# SMC1940-A.net
KiCad netlist of a schematic drawn in Altium Designer
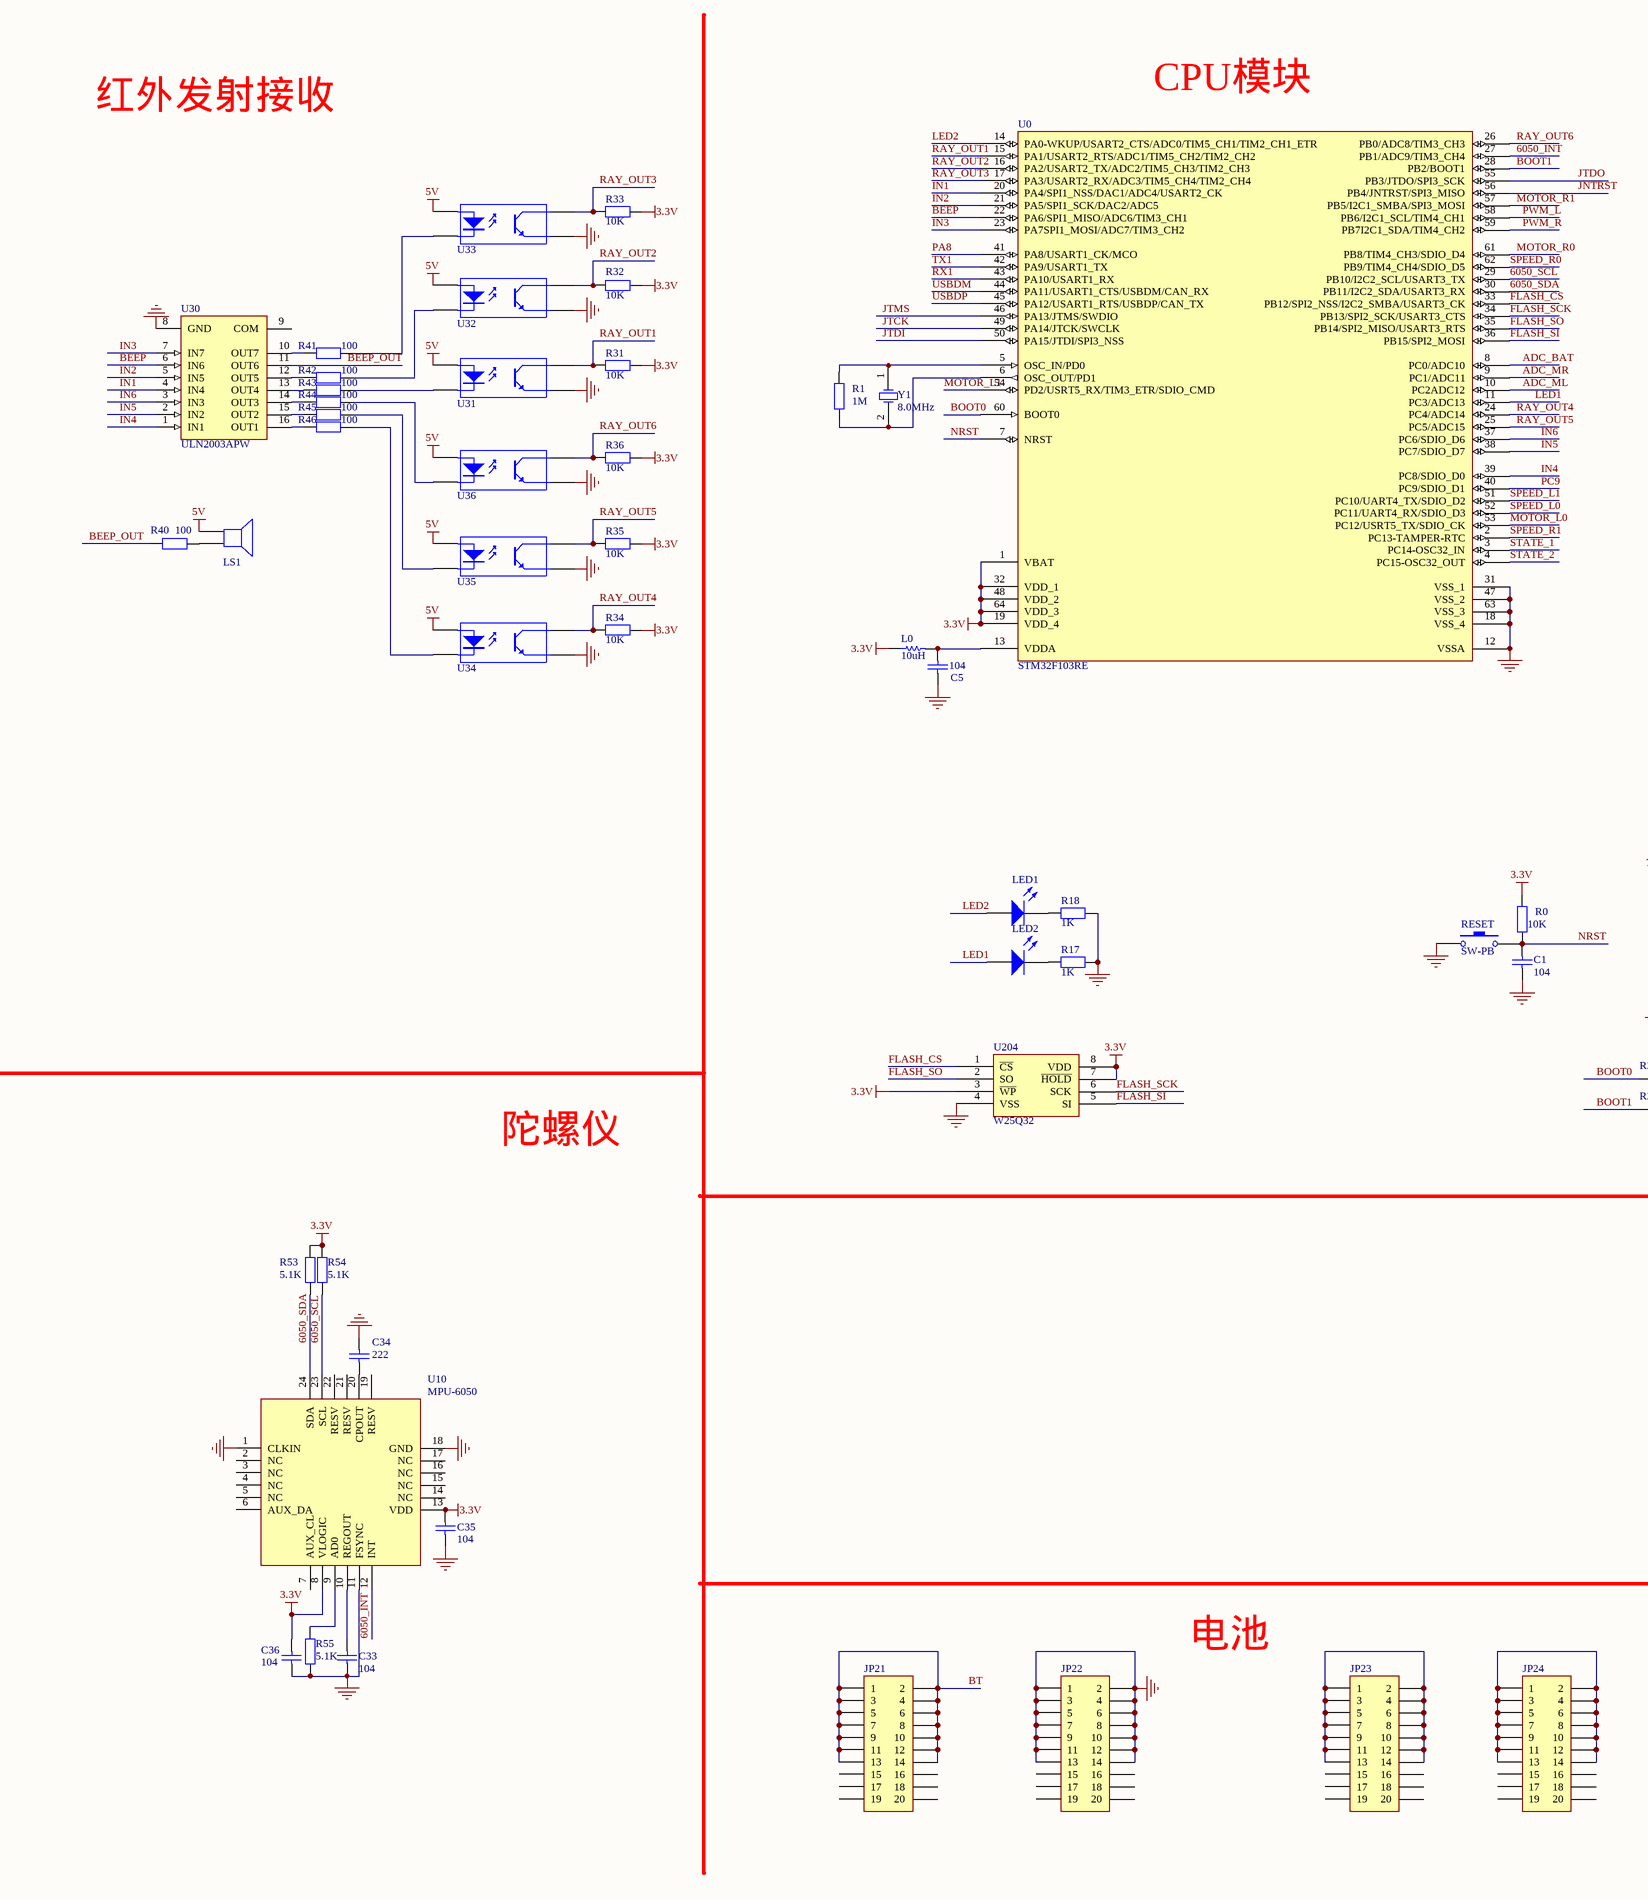
[diagram p0: SMC1940-A.SCHDOC, left]
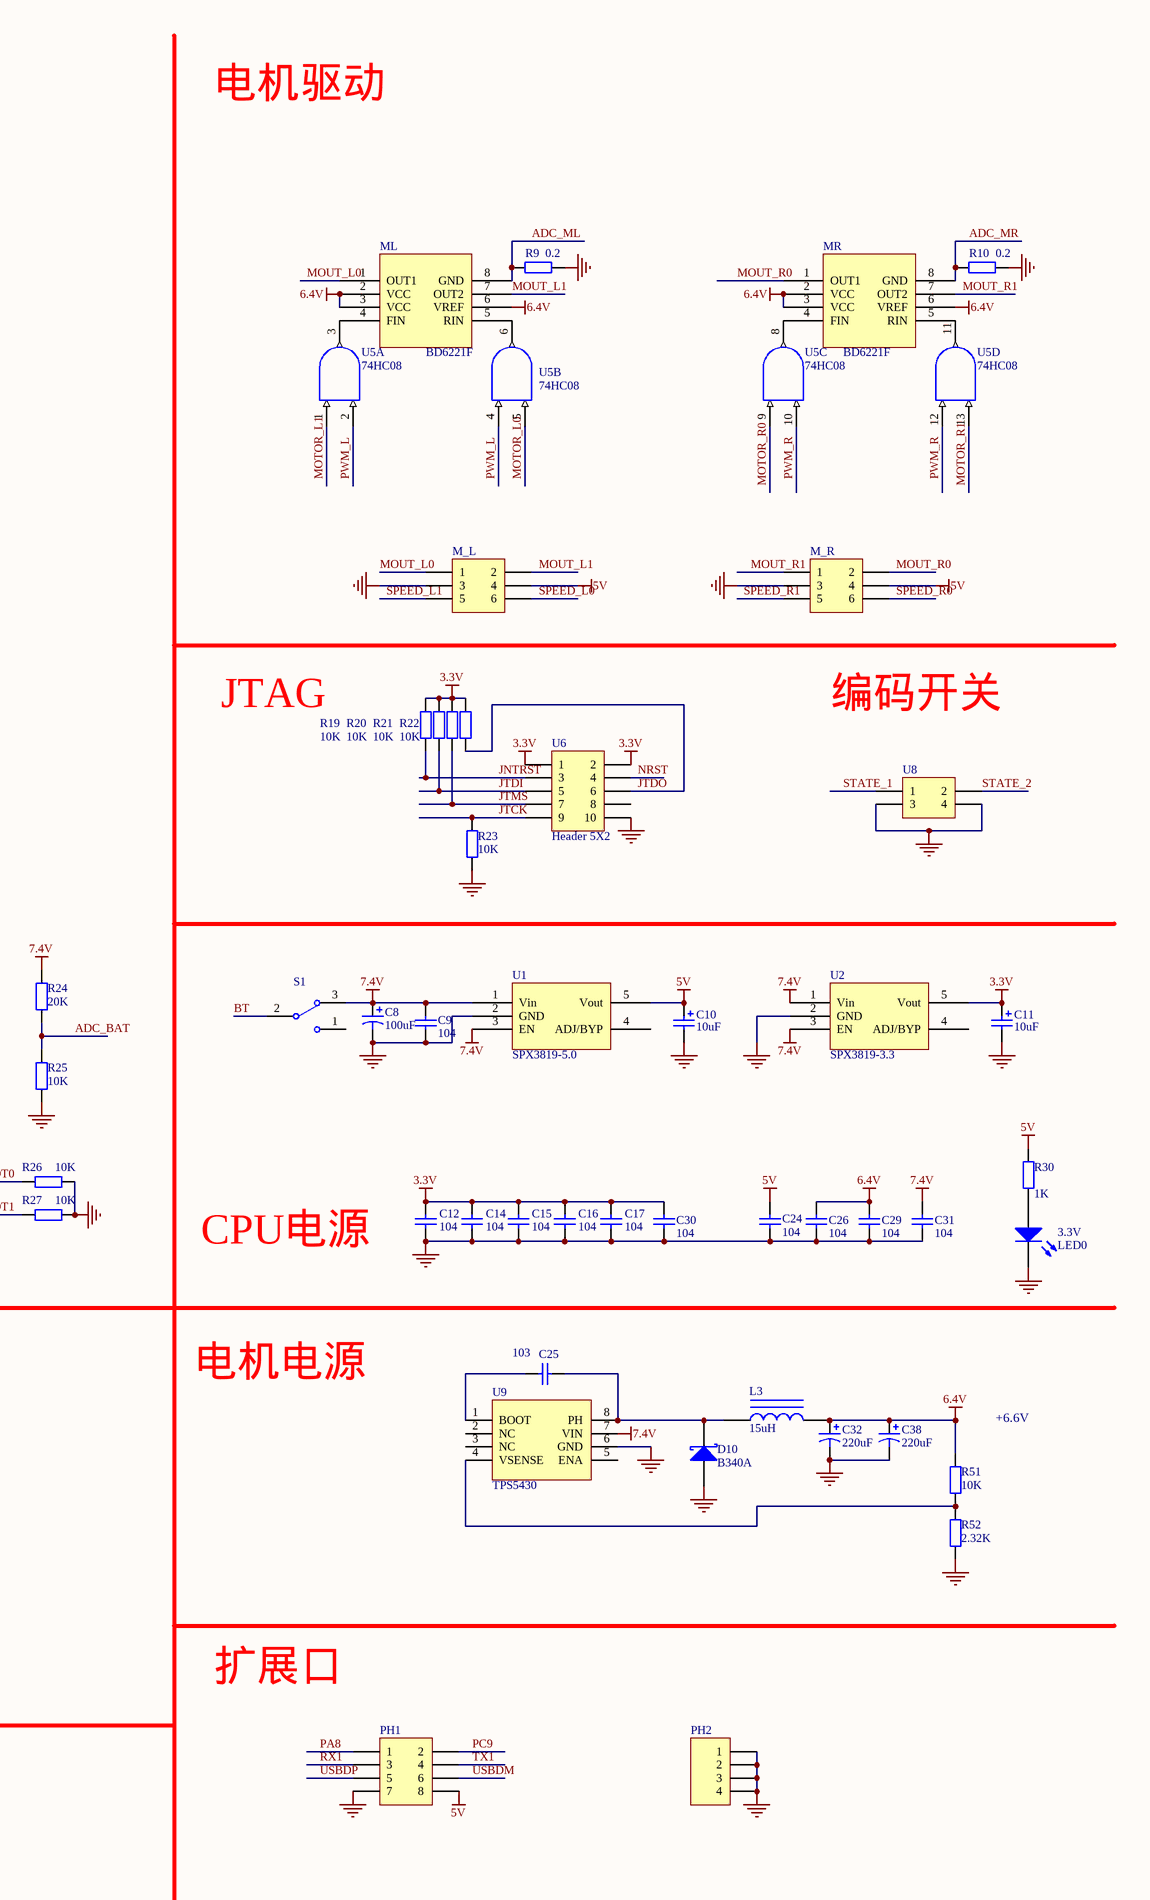
[diagram p1: SMC1940-A.SCHDOC, right]

(export (version "E")
  (design (tool "Eeschema 10.0.6"))
  (components
    (comp (ref "3.3V")
      (value "LED0")
      (footprint "YU-SMD0603")
      (description "Typical INFRARED GaAs LED")
      (fields (field (name "PUBLISHER") "Altium Limited"))
      (libsource (lib "Miscellaneous Devices") (part "LED0"))
    )
    (comp (ref "C1")
      (value "104")
      (footprint "YU-SMD0603")
      (description "Capacitor")
      (fields (field (name "PUBLISHER") "Altium Limited"))
      (libsource (lib "Miscellaneous Devices") (part "Cap"))
    )
    (comp (ref "C5")
      (value "104")
      (footprint "YU-SMD0603")
      (description "Capacitor")
      (fields (field (name "PUBLISHER") "Altium Limited"))
      (libsource (lib "Miscellaneous Devices") (part "Cap"))
    )
    (comp (ref "C8")
      (value "100uF")
      (footprint "CAPPR2.5-6.3X5")
      (description "Polarized Capacitor (Axial)")
      (fields (field (name "PUBLISHER") "Altium Limited"))
      (libsource (lib "Miscellaneous Devices") (part "Cap Pol2"))
    )
    (comp (ref "C9")
      (value "104")
      (footprint "YU-SMD0603")
      (description "Capacitor")
      (fields (field (name "PUBLISHER") "Altium Limited"))
      (libsource (lib "Miscellaneous Devices") (part "Cap"))
    )
    (comp (ref "C10")
      (value "10uF")
      (footprint "YU-SMD0805")
      (description "Polarized Capacitor (Radial)")
      (fields
        (field (name "MANUFACTURER") "Generic Components")
        (field (name "PUBLISHER") "Altium Hobart Technology Centre")
      )
      (libsource (lib "Miscellaneous Devices") (part "Cap Pol1"))
    )
    (comp (ref "C11")
      (value "10uF")
      (footprint "YU-SMD0805")
      (description "Polarized Capacitor (Radial)")
      (fields
        (field (name "MANUFACTURER") "Generic Components")
        (field (name "PUBLISHER") "Altium Hobart Technology Centre")
      )
      (libsource (lib "Miscellaneous Devices") (part "Cap Pol1"))
    )
    (comp (ref "C12")
      (value "104")
      (footprint "YU-SMD0603")
      (description "Capacitor")
      (fields (field (name "PUBLISHER") "Altium Limited"))
      (libsource (lib "Miscellaneous Devices") (part "Cap"))
    )
    (comp (ref "C14")
      (value "104")
      (footprint "YU-SMD0603")
      (description "Capacitor")
      (fields (field (name "PUBLISHER") "Altium Limited"))
      (libsource (lib "Miscellaneous Devices") (part "Cap"))
    )
    (comp (ref "C15")
      (value "104")
      (footprint "YU-SMD0603")
      (description "Capacitor")
      (fields (field (name "PUBLISHER") "Altium Limited"))
      (libsource (lib "Miscellaneous Devices") (part "Cap"))
    )
    (comp (ref "C16")
      (value "104")
      (footprint "YU-SMD0603")
      (description "Capacitor")
      (fields (field (name "PUBLISHER") "Altium Limited"))
      (libsource (lib "Miscellaneous Devices") (part "Cap"))
    )
    (comp (ref "C17")
      (value "104")
      (footprint "YU-SMD0603")
      (description "Capacitor")
      (fields (field (name "PUBLISHER") "Altium Limited"))
      (libsource (lib "Miscellaneous Devices") (part "Cap"))
    )
    (comp (ref "C24")
      (value "104")
      (footprint "YU-SMD0603")
      (description "Capacitor")
      (fields (field (name "PUBLISHER") "Altium Limited"))
      (libsource (lib "Miscellaneous Devices") (part "Cap"))
    )
    (comp (ref "C25")
      (value "103")
      (footprint "YU-SMD0603")
      (description "Capacitor")
      (fields (field (name "PUBLISHER") "Altium Limited"))
      (libsource (lib "Miscellaneous Devices") (part "Cap"))
    )
    (comp (ref "C26")
      (value "104")
      (footprint "YU-SMD0603")
      (description "Capacitor")
      (fields (field (name "PUBLISHER") "Altium Limited"))
      (libsource (lib "Miscellaneous Devices") (part "Cap"))
    )
    (comp (ref "C29")
      (value "104")
      (footprint "YU-SMD0603")
      (description "Capacitor")
      (fields (field (name "PUBLISHER") "Altium Limited"))
      (libsource (lib "Miscellaneous Devices") (part "Cap"))
    )
    (comp (ref "C30")
      (value "104")
      (footprint "YU-SMD0603")
      (description "Capacitor")
      (fields (field (name "PUBLISHER") "Altium Limited"))
      (libsource (lib "Miscellaneous Devices") (part "Cap"))
    )
    (comp (ref "C31")
      (value "104")
      (footprint "YU-SMD0603")
      (description "Capacitor")
      (fields (field (name "PUBLISHER") "Altium Limited"))
      (libsource (lib "Miscellaneous Devices") (part "Cap"))
    )
    (comp (ref "C32")
      (value "220uF")
      (footprint "CAPPR2.5-6.3X5")
      (description "Polarized Capacitor (Axial)")
      (fields (field (name "PUBLISHER") "Altium Limited"))
      (libsource (lib "Miscellaneous Devices") (part "Cap Pol2"))
    )
    (comp (ref "C33")
      (value "104")
      (footprint "YU-SMD0603")
      (description "Capacitor")
      (fields (field (name "PUBLISHER") "Altium Limited"))
      (libsource (lib "Miscellaneous Devices") (part "Cap"))
    )
    (comp (ref "C34")
      (value "222")
      (footprint "YU-SMD0603")
      (description "Capacitor")
      (fields (field (name "PUBLISHER") "Altium Limited"))
      (libsource (lib "Miscellaneous Devices") (part "Cap"))
    )
    (comp (ref "C35")
      (value "104")
      (footprint "YU-SMD0603")
      (description "Capacitor")
      (fields (field (name "PUBLISHER") "Altium Limited"))
      (libsource (lib "Miscellaneous Devices") (part "Cap"))
    )
    (comp (ref "C36")
      (value "104")
      (footprint "YU-SMD0603")
      (description "Capacitor")
      (fields (field (name "PUBLISHER") "Altium Limited"))
      (libsource (lib "Miscellaneous Devices") (part "Cap"))
    )
    (comp (ref "C38")
      (value "220uF")
      (footprint "CAPPR2.5-6.3X5")
      (description "Polarized Capacitor (Axial)")
      (fields (field (name "PUBLISHER") "Altium Limited"))
      (libsource (lib "Miscellaneous Devices") (part "Cap Pol2"))
    )
    (comp (ref "D10")
      (value "B340A")
      (footprint "DO-214")
      (description "Schottky Rectifier")
      (fields (field (name "PUBLISHER") "Altium Limited"))
      (libsource (lib "Miscellaneous Devices") (part "Diode 11DQ03"))
    )
    (comp (ref "JP21")
      (value "~")
      (footprint "MSHDR2X10")
      (description "Header, 10-Pin, Dual row")
      (fields (field (name "PUBLISHER") "Altium Limited"))
      (libsource (lib "Miscellaneous Connectors") (part "MHDR2X10"))
    )
    (comp (ref "JP22")
      (value "~")
      (footprint "MSHDR2X10")
      (description "Header, 10-Pin, Dual row")
      (fields (field (name "PUBLISHER") "Altium Limited"))
      (libsource (lib "Miscellaneous Connectors") (part "MHDR2X10"))
    )
    (comp (ref "JP23")
      (value "~")
      (footprint "MSHDR2X10")
      (description "Header, 10-Pin, Dual row")
      (fields (field (name "PUBLISHER") "Altium Limited"))
      (libsource (lib "Miscellaneous Connectors") (part "MHDR2X10"))
    )
    (comp (ref "JP24")
      (value "~")
      (footprint "MSHDR2X10")
      (description "Header, 10-Pin, Dual row")
      (fields (field (name "PUBLISHER") "Altium Limited"))
      (libsource (lib "Miscellaneous Connectors") (part "MHDR2X10"))
    )
    (comp (ref "L0")
      (value "10uH")
      (footprint "YU-SMD0603")
      (description "Resistor")
      (fields (field (name "PUBLISHER") "Altium Limited"))
      (libsource (lib "Miscellaneous Devices") (part "Res1"))
    )
    (comp (ref "L3")
      (value "15uH")
      (footprint "HC0603")
      (description "Magnetic-Core Inductor")
      (fields (field (name "PUBLISHER") "Altium Limited"))
      (libsource (lib "Miscellaneous Devices") (part "Inductor Iron"))
    )
    (comp (ref "LED1")
      (value "LED0")
      (footprint "YU-SMD0603")
      (description "Typical INFRARED GaAs LED")
      (fields (field (name "PUBLISHER") "Altium Limited"))
      (libsource (lib "Miscellaneous Devices") (part "LED0"))
    )
    (comp (ref "LED2")
      (value "~")
      (footprint "YU-SMD0603")
      (description "Typical INFRARED GaAs LED")
      (fields (field (name "PUBLISHER") "Altium Limited"))
      (libsource (lib "Miscellaneous Devices") (part "LED0"))
    )
    (comp (ref "LS1")
      (value "~")
      (footprint "蜂鸣器5020")
      (description "Loudspeaker")
      (fields (field (name "PUBLISHER") "Altium Limited"))
      (libsource (lib "Miscellaneous Devices") (part "Speaker"))
    )
    (comp (ref "ML") (value "BD6221F") (footprint "SO-G8") (libsource (lib "yu") (part "BD6221F")))
    (comp (ref "MR") (value "BD6221F") (footprint "SO-G8") (libsource (lib "yu") (part "BD6221F")))
    (comp (ref "M_L")
      (value "~")
      (footprint "DC3-6PS")
      (description "Header, 3-Pin, Dual row")
      (fields (field (name "PUBLISHER") "Altium Limited"))
      (libsource (lib "Miscellaneous Connectors") (part "Header 3X2"))
    )
    (comp (ref "M_R")
      (value "~")
      (footprint "DC3-6PS")
      (description "Header, 3-Pin, Dual row")
      (fields (field (name "PUBLISHER") "Altium Limited"))
      (libsource (lib "Miscellaneous Connectors") (part "Header 3X2"))
    )
    (comp (ref "PH1")
      (value "~")
      (footprint "HDR2X4")
      (description "Header, 4-Pin, Dual row")
      (fields (field (name "PUBLISHER") "Altium Limited"))
      (libsource (lib "Miscellaneous Connectors") (part "Header 4X2"))
    )
    (comp (ref "PH2")
      (value "Header 4")
      (footprint "HDR1X4")
      (description "Header, 4-Pin")
      (fields (field (name "PUBLISHER") "Altium Limited"))
      (libsource (lib "Miscellaneous Connectors") (part "Header 4"))
    )
    (comp (ref "R0")
      (value "10K")
      (footprint "YU-SMD0603")
      (description "Resistor")
      (fields (field (name "PUBLISHER") "Altium Limited"))
      (libsource (lib "") (part "Res2_3"))
    )
    (comp (ref "R1")
      (value "1M")
      (footprint "YU-SMD0603")
      (description "Resistor")
      (fields (field (name "PUBLISHER") "Altium Limited"))
      (libsource (lib "") (part "Res2_3"))
    )
    (comp (ref "R9")
      (value "0.2")
      (footprint "YU-SMD1206")
      (description "Resistor")
      (fields (field (name "PUBLISHER") "Altium Limited"))
      (libsource (lib "") (part "Res2_1"))
    )
    (comp (ref "R10")
      (value "0.2")
      (footprint "YU-SMD1206")
      (description "Resistor")
      (fields (field (name "PUBLISHER") "Altium Limited"))
      (libsource (lib "") (part "Res2_1"))
    )
    (comp (ref "R17")
      (value "1K")
      (footprint "YU-SMD0603")
      (description "Resistor")
      (fields (field (name "PUBLISHER") "Altium Limited"))
      (libsource (lib "") (part "Res2_5"))
    )
    (comp (ref "R18")
      (value "1K")
      (footprint "YU-SMD0603")
      (description "Resistor")
      (fields (field (name "PUBLISHER") "Altium Limited"))
      (libsource (lib "") (part "Res2_5"))
    )
    (comp (ref "R19")
      (value "10K")
      (footprint "YU-SMD0603")
      (description "Resistor")
      (fields (field (name "PUBLISHER") "Altium Limited"))
      (libsource (lib "") (part "Res2_2"))
    )
    (comp (ref "R20")
      (value "10K")
      (footprint "YU-SMD0603")
      (description "Resistor")
      (fields (field (name "PUBLISHER") "Altium Limited"))
      (libsource (lib "") (part "Res2_2"))
    )
    (comp (ref "R21")
      (value "10K")
      (footprint "YU-SMD0603")
      (description "Resistor")
      (fields (field (name "PUBLISHER") "Altium Limited"))
      (libsource (lib "") (part "Res2_2"))
    )
    (comp (ref "R22")
      (value "10K")
      (footprint "YU-SMD0603")
      (description "Resistor")
      (fields (field (name "PUBLISHER") "Altium Limited"))
      (libsource (lib "") (part "Res2_2"))
    )
    (comp (ref "R23")
      (value "10K")
      (footprint "YU-SMD0603")
      (description "Resistor")
      (fields (field (name "PUBLISHER") "Altium Limited"))
      (libsource (lib "") (part "Res2_2"))
    )
    (comp (ref "R24")
      (value "20K")
      (footprint "YU-SMD0603")
      (description "Resistor")
      (fields (field (name "PUBLISHER") "Altium Limited"))
      (libsource (lib "") (part "Res2_4"))
    )
    (comp (ref "R25")
      (value "10K")
      (footprint "YU-SMD0603")
      (description "Resistor")
      (fields (field (name "PUBLISHER") "Altium Limited"))
      (libsource (lib "") (part "Res2_4"))
    )
    (comp (ref "R26")
      (value "10K")
      (footprint "YU-SMD0603")
      (description "Resistor")
      (fields (field (name "PUBLISHER") "Altium Limited"))
      (libsource (lib "") (part "Res2_5"))
    )
    (comp (ref "R27")
      (value "10K")
      (footprint "YU-SMD0603")
      (description "Resistor")
      (fields (field (name "PUBLISHER") "Altium Limited"))
      (libsource (lib "") (part "Res2_5"))
    )
    (comp (ref "R30")
      (value "1K")
      (footprint "YU-SMD0603")
      (description "Resistor")
      (fields (field (name "PUBLISHER") "Altium Limited"))
      (libsource (lib "") (part "Res2_3"))
    )
    (comp (ref "R31")
      (value "10K")
      (footprint "YU-SMD0603")
      (description "Resistor")
      (fields (field (name "PUBLISHER") "Altium Limited"))
      (libsource (lib "Miscellaneous Devices") (part "Res2"))
    )
    (comp (ref "R32")
      (value "10K")
      (footprint "YU-SMD0603")
      (description "Resistor")
      (fields (field (name "PUBLISHER") "Altium Limited"))
      (libsource (lib "Miscellaneous Devices") (part "Res2"))
    )
    (comp (ref "R33")
      (value "10K")
      (footprint "YU-SMD0603")
      (description "Resistor")
      (fields (field (name "PUBLISHER") "Altium Limited"))
      (libsource (lib "Miscellaneous Devices") (part "Res2"))
    )
    (comp (ref "R34")
      (value "10K")
      (footprint "YU-SMD0603")
      (description "Resistor")
      (fields (field (name "PUBLISHER") "Altium Limited"))
      (libsource (lib "Miscellaneous Devices") (part "Res2"))
    )
    (comp (ref "R35")
      (value "10K")
      (footprint "YU-SMD0603")
      (description "Resistor")
      (fields (field (name "PUBLISHER") "Altium Limited"))
      (libsource (lib "Miscellaneous Devices") (part "Res2"))
    )
    (comp (ref "R36")
      (value "10K")
      (footprint "YU-SMD0603")
      (description "Resistor")
      (fields (field (name "PUBLISHER") "Altium Limited"))
      (libsource (lib "Miscellaneous Devices") (part "Res2"))
    )
    (comp (ref "R40")
      (value "100")
      (footprint "YU-SMD0805")
      (description "Resistor")
      (fields (field (name "PUBLISHER") "Altium Limited"))
      (libsource (lib "") (part "Res2_1"))
    )
    (comp (ref "R41")
      (value "100")
      (footprint "YU-SMD0805")
      (description "Resistor")
      (fields (field (name "PUBLISHER") "Altium Limited"))
      (libsource (lib "") (part "Res2_1"))
    )
    (comp (ref "R42")
      (value "100")
      (footprint "YU-SMD0805")
      (description "Resistor")
      (fields (field (name "PUBLISHER") "Altium Limited"))
      (libsource (lib "") (part "Res2_1"))
    )
    (comp (ref "R43")
      (value "100")
      (footprint "YU-SMD0805")
      (description "Resistor")
      (fields (field (name "PUBLISHER") "Altium Limited"))
      (libsource (lib "") (part "Res2_1"))
    )
    (comp (ref "R44")
      (value "100")
      (footprint "YU-SMD0805")
      (description "Resistor")
      (fields (field (name "PUBLISHER") "Altium Limited"))
      (libsource (lib "") (part "Res2_1"))
    )
    (comp (ref "R45")
      (value "100")
      (footprint "YU-SMD0805")
      (description "Resistor")
      (fields (field (name "PUBLISHER") "Altium Limited"))
      (libsource (lib "") (part "Res2_1"))
    )
    (comp (ref "R46")
      (value "100")
      (footprint "YU-SMD0805")
      (description "Resistor")
      (fields (field (name "PUBLISHER") "Altium Limited"))
      (libsource (lib "") (part "Res2_1"))
    )
    (comp (ref "R51")
      (value "10K")
      (footprint "YU-SMD0603")
      (description "Resistor")
      (fields (field (name "PUBLISHER") "Altium Limited"))
      (libsource (lib "") (part "Res2_3"))
    )
    (comp (ref "R52")
      (value "2.32K")
      (footprint "YU-SMD0603")
      (description "Resistor")
      (fields (field (name "PUBLISHER") "Altium Limited"))
      (libsource (lib "") (part "Res2_3"))
    )
    (comp (ref "R53")
      (value "5.1K")
      (footprint "YU-SMD0603")
      (description "Resistor")
      (fields (field (name "PUBLISHER") "Altium Limited"))
      (libsource (lib "") (part "Res2_3"))
    )
    (comp (ref "R54")
      (value "5.1K")
      (footprint "YU-SMD0603")
      (description "Resistor")
      (fields (field (name "PUBLISHER") "Altium Limited"))
      (libsource (lib "") (part "Res2_3"))
    )
    (comp (ref "R55")
      (value "5.1K")
      (footprint "YU-SMD0603")
      (description "Resistor")
      (fields (field (name "PUBLISHER") "Altium Limited"))
      (libsource (lib "") (part "Res2_3"))
    )
    (comp (ref "RESET")
      (value "SW-PB")
      (footprint "KEY3*6C")
      (description "Switch")
      (fields (field (name "PUBLISHER") "Altium Limited"))
      (libsource (lib "Miscellaneous Devices") (part "SW-PB"))
    )
    (comp (ref "S1")
      (value "~")
      (footprint "SWITCH_L")
      (description "SPDT Subminiature Toggle Switch, Right Angle Mounting, Vertical Actuation")
      (fields (field (name "PUBLISHER") "Altium Limited"))
      (libsource (lib "Miscellaneous Devices") (part "SW-SPDT"))
    )
    (comp (ref "U0")
      (value "STM32F103RE")
      (footprint "LQFP64_N")
      (description "STM32 ARM-based 32-bit MCU with 128 Kbytes Flash, 64-pin LQFP, Industrial Temperature")
      (fields (field (name "PUBLISHER") "*"))
      (libsource (lib "ST Microcontroller 32-Bit STM32 SCH") (part "STM32F101RC"))
    )
    (comp (ref "U1") (value "SPX3819-5.0") (footprint "YU-SOT23-5") (libsource (lib "yu") (part "SP6201")))
    (comp (ref "U2") (value "SPX3819-3.3") (footprint "YU-SOT23-5") (libsource (lib "yu") (part "SP6201")))
    (comp (ref "U5")
      (value "74HC08")
      (footprint "TSSO5x6-G14/X.3")
      (description "Quad 2-Input AND Gate")
      (fields (field (name "PUBLISHER") "Altium Limited"))
      (libsource (lib "Motorola Logic Gate") (part "MC74HC08AD"))
    )
    (comp (ref "U6")
      (value "Header 5X2")
      (footprint "DownLoad2-2*5")
      (description "Header, 5-Pin, Dual row")
      (fields (field (name "PUBLISHER") "Altium Limited"))
      (libsource (lib "Miscellaneous Connectors") (part "Header 5X2"))
    )
    (comp (ref "U8")
      (value "~")
      (footprint "SW-2")
      (description "Header, 2-Pin, Dual row")
      (fields (field (name "PUBLISHER") "Altium Limited"))
      (libsource (lib "Miscellaneous Connectors") (part "Header 2X2"))
    )
    (comp (ref "U9") (value "TPS5430") (footprint "SO-G8") (libsource (lib "yu") (part "TPS2430")))
    (comp (ref "U10") (value "MPU-6050") (footprint "QFN-24") (libsource (lib "yu") (part "MPU-6050")))
    (comp (ref "U30")
      (value "ULN2003APW")
      (footprint "TSSO5x6-G16")
      (description "Seven Darlington Array")
      (fields (field (name "PUBLISHER") "Altium Limited"))
      (libsource (lib "ST Interface Darlington Driver") (part "ULN2003D"))
    )
    (comp (ref "U31") (value "~") (footprint "F5-2") (libsource (lib "yu") (part "光耦2")))
    (comp (ref "U32") (value "~") (footprint "F5-2") (libsource (lib "yu") (part "光耦2")))
    (comp (ref "U33") (value "~") (footprint "F5-2") (libsource (lib "yu") (part "光耦2")))
    (comp (ref "U34") (value "~") (footprint "F5-2") (libsource (lib "yu") (part "光耦2")))
    (comp (ref "U35") (value "~") (footprint "F5-2") (libsource (lib "yu") (part "光耦2")))
    (comp (ref "U36") (value "~") (footprint "F5-2") (libsource (lib "yu") (part "光耦2")))
    (comp (ref "U204") (value "W25Q32") (footprint "sop8") (libsource (lib "yu") (part "FM25H20")))
    (comp (ref "Y1")
      (value "8.0MHz")
      (footprint "晶振3213")
      (description "Crystal Oscillator")
      (fields (field (name "Comment") "XTAL") (field (name "PUBLISHER") "Altium Limited"))
      (libsource (lib "Miscellaneous Devices") (part "XTAL"))
    )
  )
  (nets
    (net (code "1") (name "/6050_INT") (class "Default")
      (node (ref "U0") (pin "27") (pinfunction "PB1/ADC9/TIM3_CH4_27") (pintype "bidirectional"))
      (node (ref "U10") (pin "12") (pinfunction "INT_12") (pintype "passive"))
    )
    (net (code "2") (name "/6050_SCL") (class "Default")
      (node (ref "R54") (pin "1") (pinfunction "1_1") (pintype "passive"))
      (node (ref "U0") (pin "29") (pinfunction "PB10/I2C2_SCL/USART3_TX_29") (pintype "bidirectional"))
      (node (ref "U10") (pin "23") (pinfunction "SCL_23") (pintype "passive"))
    )
    (net (code "3") (name "/6050_SDA") (class "Default")
      (node (ref "R53") (pin "1") (pinfunction "1_1") (pintype "passive"))
      (node (ref "U0") (pin "30") (pinfunction "PB11/I2C2_SDA/USART3_RX_30") (pintype "bidirectional"))
      (node (ref "U10") (pin "24") (pinfunction "SDA_24") (pintype "passive"))
    )
    (net (code "4") (name "/ADC_BAT") (class "Default")
      (node (ref "R24") (pin "1") (pinfunction "1_1") (pintype "passive"))
      (node (ref "R25") (pin "2") (pinfunction "2_2") (pintype "passive"))
      (node (ref "U0") (pin "8") (pinfunction "PC0/ADC10_8") (pintype "bidirectional"))
    )
    (net (code "5") (name "/ADC_ML") (class "Default")
      (node (ref "ML") (pin "8") (pinfunction "GND_8") (pintype "passive"))
      (node (ref "R9") (pin "1") (pinfunction "1_1") (pintype "passive"))
      (node (ref "U0") (pin "10") (pinfunction "PC2ADC12_10") (pintype "bidirectional"))
    )
    (net (code "6") (name "/ADC_MR") (class "Default")
      (node (ref "MR") (pin "8") (pinfunction "GND_8") (pintype "passive"))
      (node (ref "R10") (pin "1") (pinfunction "1_1") (pintype "passive"))
      (node (ref "U0") (pin "9") (pinfunction "PC1/ADC11_9") (pintype "bidirectional"))
    )
    (net (code "7") (name "/BEEP") (class "Default")
      (node (ref "U0") (pin "22") (pinfunction "PA6/SPI1_MISO/ADC6/TIM3_CH1_22") (pintype "bidirectional"))
      (node (ref "U30") (pin "6") (pinfunction "IN6_6") (pintype "input"))
    )
    (net (code "8") (name "/BEEP_OUT") (class "Default")
      (node (ref "R40") (pin "1") (pinfunction "1_1") (pintype "passive"))
      (node (ref "U30") (pin "11") (pinfunction "OUT6_11") (pintype "open_collector"))
    )
    (net (code "9") (name "/BOOT0") (class "Default")
      (node (ref "R26") (pin "1") (pinfunction "1_1") (pintype "passive"))
      (node (ref "U0") (pin "60") (pinfunction "BOOT0_60") (pintype "input"))
    )
    (net (code "10") (name "/BOOT1") (class "Default")
      (node (ref "R27") (pin "1") (pinfunction "1_1") (pintype "passive"))
      (node (ref "U0") (pin "28") (pinfunction "PB2/BOOT1_28") (pintype "bidirectional"))
    )
    (net (code "11") (name "/BT") (class "Default")
      (node (ref "JP21") (pin "1") (pinfunction "1_1") (pintype "passive"))
      (node (ref "JP21") (pin "10") (pinfunction "10_10") (pintype "passive"))
      (node (ref "JP21") (pin "11") (pinfunction "11_11") (pintype "passive"))
      (node (ref "JP21") (pin "12") (pinfunction "12_12") (pintype "passive"))
      (node (ref "JP21") (pin "13") (pinfunction "13_13") (pintype "passive"))
      (node (ref "JP21") (pin "14") (pinfunction "14_14") (pintype "passive"))
      (node (ref "JP21") (pin "2") (pinfunction "2_2") (pintype "passive"))
      (node (ref "JP21") (pin "3") (pinfunction "3_3") (pintype "passive"))
      (node (ref "JP21") (pin "4") (pinfunction "4_4") (pintype "passive"))
      (node (ref "JP21") (pin "5") (pinfunction "5_5") (pintype "passive"))
      (node (ref "JP21") (pin "6") (pinfunction "6_6") (pintype "passive"))
      (node (ref "JP21") (pin "7") (pinfunction "7_7") (pintype "passive"))
      (node (ref "JP21") (pin "8") (pinfunction "8_8") (pintype "passive"))
      (node (ref "JP21") (pin "9") (pinfunction "9_9") (pintype "passive"))
      (node (ref "S1") (pin "2") (pintype "passive"))
    )
    (net (code "12") (name "/FLASH_CS") (class "Default")
      (node (ref "U0") (pin "33") (pinfunction "PB12/SPI2_NSS/I2C2_SMBA/USART3_CK_33") (pintype "bidirectional"))
      (node (ref "U204") (pin "1") (pinfunction "~{CS}_1") (pintype "passive"))
    )
    (net (code "13") (name "/FLASH_SCK") (class "Default")
      (node (ref "U0") (pin "34") (pinfunction "PB13/SPI2_SCK/USART3_CTS_34") (pintype "bidirectional"))
      (node (ref "U204") (pin "6") (pinfunction "SCK_6") (pintype "passive"))
    )
    (net (code "14") (name "/FLASH_SI") (class "Default")
      (node (ref "U0") (pin "36") (pinfunction "PB15/SPI2_MOSI_36") (pintype "bidirectional"))
      (node (ref "U204") (pin "5") (pinfunction "SI_5") (pintype "passive"))
    )
    (net (code "15") (name "/FLASH_SO") (class "Default")
      (node (ref "U0") (pin "35") (pinfunction "PB14/SPI2_MISO/USART3_RTS_35") (pintype "bidirectional"))
      (node (ref "U204") (pin "2") (pinfunction "SO_2") (pintype "passive"))
    )
    (net (code "16") (name "/IN1") (class "Default")
      (node (ref "U0") (pin "20") (pinfunction "PA4/SPI1_NSS/DAC1/ADC4/USART2_CK_20") (pintype "bidirectional"))
      (node (ref "U30") (pin "4") (pinfunction "IN4_4") (pintype "input"))
    )
    (net (code "17") (name "/IN2") (class "Default")
      (node (ref "U0") (pin "21") (pinfunction "PA5/SPI1_SCK/DAC2/ADC5_21") (pintype "bidirectional"))
      (node (ref "U30") (pin "5") (pinfunction "IN5_5") (pintype "input"))
    )
    (net (code "18") (name "/IN3") (class "Default")
      (node (ref "U0") (pin "23") (pinfunction "PA7SPI1_MOSI/ADC7/TIM3_CH2_23") (pintype "bidirectional"))
      (node (ref "U30") (pin "7") (pinfunction "IN7_7") (pintype "input"))
    )
    (net (code "19") (name "/IN4") (class "Default")
      (node (ref "U0") (pin "39") (pinfunction "PC8/SDIO_D0_39") (pintype "bidirectional"))
      (node (ref "U30") (pin "1") (pinfunction "IN1_1") (pintype "input"))
    )
    (net (code "20") (name "/IN5") (class "Default")
      (node (ref "U0") (pin "38") (pinfunction "PC7/SDIO_D7_38") (pintype "bidirectional"))
      (node (ref "U30") (pin "2") (pinfunction "IN2_2") (pintype "input"))
    )
    (net (code "21") (name "/IN6") (class "Default")
      (node (ref "U0") (pin "37") (pinfunction "PC6/SDIO_D6_37") (pintype "bidirectional"))
      (node (ref "U30") (pin "3") (pinfunction "IN3_3") (pintype "input"))
    )
    (net (code "22") (name "/JNTRST") (class "Default")
      (node (ref "R19") (pin "1") (pinfunction "1_1") (pintype "passive"))
      (node (ref "U0") (pin "56") (pinfunction "PB4/JNTRST/SPI3_MISO_56") (pintype "bidirectional"))
      (node (ref "U6") (pin "3") (pinfunction "3_3") (pintype "passive"))
    )
    (net (code "23") (name "/JTCK") (class "Default")
      (node (ref "R23") (pin "2") (pinfunction "2_2") (pintype "passive"))
      (node (ref "U0") (pin "49") (pinfunction "PA14/JTCK/SWCLK_49") (pintype "bidirectional"))
      (node (ref "U6") (pin "9") (pinfunction "9_9") (pintype "passive"))
    )
    (net (code "24") (name "/JTDI") (class "Default")
      (node (ref "R20") (pin "1") (pinfunction "1_1") (pintype "passive"))
      (node (ref "U0") (pin "50") (pinfunction "PA15/JTDI/SPI3_NSS_50") (pintype "bidirectional"))
      (node (ref "U6") (pin "5") (pinfunction "5_5") (pintype "passive"))
    )
    (net (code "25") (name "/JTDO") (class "Default")
      (node (ref "R22") (pin "1") (pinfunction "1_1") (pintype "passive"))
      (node (ref "U0") (pin "55") (pinfunction "PB3/JTDO/SPI3_SCK_55") (pintype "bidirectional"))
      (node (ref "U6") (pin "6") (pinfunction "6_6") (pintype "passive"))
    )
    (net (code "26") (name "/JTMS") (class "Default")
      (node (ref "R21") (pin "1") (pinfunction "1_1") (pintype "passive"))
      (node (ref "U0") (pin "46") (pinfunction "PA13/JTMS/SWDIO_46") (pintype "bidirectional"))
      (node (ref "U6") (pin "7") (pinfunction "7_7") (pintype "passive"))
    )
    (net (code "27") (name "/LED1") (class "Default")
      (node (ref "LED2") (pin "1") (pinfunction "A_1") (pintype "passive"))
      (node (ref "U0") (pin "11") (pinfunction "PC3/ADC13_11") (pintype "bidirectional"))
    )
    (net (code "28") (name "/LED2") (class "Default")
      (node (ref "LED1") (pin "1") (pinfunction "A_1") (pintype "passive"))
      (node (ref "U0") (pin "14") (pinfunction "PA0-WKUP/USART2_CTS/ADC0/TIM5_CH1/TIM2_CH1_ETR_14") (pintype "bidirectional"))
    )
    (net (code "29") (name "/MOTOR_L0") (class "Default")
      (node (ref "U0") (pin "53") (pinfunction "PC12/USRT5_TX/SDIO_CK_53") (pintype "bidirectional"))
      (node (ref "U5") (pin "5") (pinfunction "B_5") (pintype "input"))
    )
    (net (code "30") (name "/MOTOR_L1") (class "Default")
      (node (ref "U0") (pin "54") (pinfunction "PD2/USRT5_RX/TIM3_ETR/SDIO_CMD_54") (pintype "bidirectional"))
      (node (ref "U5") (pin "1") (pinfunction "A_1") (pintype "input"))
    )
    (net (code "31") (name "/MOTOR_R0") (class "Default")
      (node (ref "U0") (pin "61") (pinfunction "PB8/TIM4_CH3/SDIO_D4_61") (pintype "bidirectional"))
      (node (ref "U5") (pin "9") (pinfunction "A_9") (pintype "input"))
    )
    (net (code "32") (name "/MOTOR_R1") (class "Default")
      (node (ref "U0") (pin "57") (pinfunction "PB5/I2C1_SMBA/SPI3_MOSI_57") (pintype "bidirectional"))
      (node (ref "U5") (pin "13") (pinfunction "B_13") (pintype "input"))
    )
    (net (code "33") (name "/MOUT_L0") (class "Default")
      (node (ref "ML") (pin "1") (pinfunction "OUT1_1") (pintype "passive"))
      (node (ref "M_L") (pin "1") (pinfunction "1_1") (pintype "passive"))
    )
    (net (code "34") (name "/MOUT_L1") (class "Default")
      (node (ref "ML") (pin "7") (pinfunction "OUT2_7") (pintype "passive"))
      (node (ref "M_L") (pin "2") (pinfunction "2_2") (pintype "passive"))
    )
    (net (code "35") (name "/MOUT_R0") (class "Default")
      (node (ref "MR") (pin "1") (pinfunction "OUT1_1") (pintype "passive"))
      (node (ref "M_R") (pin "2") (pinfunction "2_2") (pintype "passive"))
    )
    (net (code "36") (name "/MOUT_R1") (class "Default")
      (node (ref "MR") (pin "7") (pinfunction "OUT2_7") (pintype "passive"))
      (node (ref "M_R") (pin "1") (pinfunction "1_1") (pintype "passive"))
    )
    (net (code "37") (name "/NRST") (class "Default")
      (node (ref "C1") (pin "2") (pinfunction "2_2") (pintype "passive"))
      (node (ref "R0") (pin "1") (pinfunction "1_1") (pintype "passive"))
      (node (ref "RESET") (pin "1") (pinfunction "1_1") (pintype "passive"))
      (node (ref "U0") (pin "7") (pinfunction "NRST_7") (pintype "bidirectional"))
      (node (ref "U6") (pin "4") (pinfunction "4_4") (pintype "passive"))
    )
    (net (code "38") (name "/PA8") (class "Default")
      (node (ref "PH1") (pin "1") (pinfunction "1_1") (pintype "passive"))
      (node (ref "U0") (pin "41") (pinfunction "PA8/USART1_CK/MCO_41") (pintype "bidirectional"))
    )
    (net (code "39") (name "/PC9") (class "Default")
      (node (ref "PH1") (pin "2") (pinfunction "2_2") (pintype "passive"))
      (node (ref "U0") (pin "40") (pinfunction "PC9/SDIO_D1_40") (pintype "bidirectional"))
    )
    (net (code "40") (name "/PWM_L") (class "Default")
      (node (ref "U0") (pin "58") (pinfunction "PB6/I2C1_SCL/TIM4_CH1_58") (pintype "bidirectional"))
      (node (ref "U5") (pin "2") (pinfunction "B_2") (pintype "input"))
      (node (ref "U5") (pin "4") (pinfunction "A_4") (pintype "input"))
    )
    (net (code "41") (name "/PWM_R") (class "Default")
      (node (ref "U0") (pin "59") (pinfunction "PB7I2C1_SDA/TIM4_CH2_59") (pintype "bidirectional"))
      (node (ref "U5") (pin "10") (pinfunction "B_10") (pintype "input"))
      (node (ref "U5") (pin "12") (pinfunction "A_12") (pintype "input"))
    )
    (net (code "42") (name "/RAY_OUT1") (class "Default")
      (node (ref "R31") (pin "2") (pinfunction "2_2") (pintype "passive"))
      (node (ref "U0") (pin "15") (pinfunction "PA1/USART2_RTS/ADC1/TIM5_CH2/TIM2_CH2_15") (pintype "bidirectional"))
      (node (ref "U31") (pin "4") (pinfunction "C_4") (pintype "passive"))
    )
    (net (code "43") (name "/RAY_OUT2") (class "Default")
      (node (ref "R32") (pin "2") (pinfunction "2_2") (pintype "passive"))
      (node (ref "U0") (pin "16") (pinfunction "PA2/USART2_TX/ADC2/TIM5_CH3/TIM2_CH3_16") (pintype "bidirectional"))
      (node (ref "U32") (pin "4") (pinfunction "C_4") (pintype "passive"))
    )
    (net (code "44") (name "/RAY_OUT3") (class "Default")
      (node (ref "R33") (pin "2") (pinfunction "2_2") (pintype "passive"))
      (node (ref "U0") (pin "17") (pinfunction "PA3/USART2_RX/ADC3/TIM5_CH4/TIM2_CH4_17") (pintype "bidirectional"))
      (node (ref "U33") (pin "4") (pinfunction "C_4") (pintype "passive"))
    )
    (net (code "45") (name "/RAY_OUT4") (class "Default")
      (node (ref "R34") (pin "2") (pinfunction "2_2") (pintype "passive"))
      (node (ref "U0") (pin "24") (pinfunction "PC4/ADC14_24") (pintype "bidirectional"))
      (node (ref "U34") (pin "4") (pinfunction "C_4") (pintype "passive"))
    )
    (net (code "46") (name "/RAY_OUT5") (class "Default")
      (node (ref "R35") (pin "2") (pinfunction "2_2") (pintype "passive"))
      (node (ref "U0") (pin "25") (pinfunction "PC5/ADC15_25") (pintype "bidirectional"))
      (node (ref "U35") (pin "4") (pinfunction "C_4") (pintype "passive"))
    )
    (net (code "47") (name "/RAY_OUT6") (class "Default")
      (node (ref "R36") (pin "2") (pinfunction "2_2") (pintype "passive"))
      (node (ref "U0") (pin "26") (pinfunction "PB0/ADC8/TIM3_CH3_26") (pintype "bidirectional"))
      (node (ref "U36") (pin "4") (pinfunction "C_4") (pintype "passive"))
    )
    (net (code "48") (name "/RX1") (class "Default")
      (node (ref "PH1") (pin "3") (pinfunction "3_3") (pintype "passive"))
      (node (ref "U0") (pin "43") (pinfunction "PA10/USART1_RX_43") (pintype "bidirectional"))
    )
    (net (code "49") (name "/SPEED_L0") (class "Default")
      (node (ref "M_L") (pin "6") (pinfunction "6_6") (pintype "passive"))
      (node (ref "U0") (pin "52") (pinfunction "PC11/UART4_RX/SDIO_D3_52") (pintype "bidirectional"))
    )
    (net (code "50") (name "/SPEED_L1") (class "Default")
      (node (ref "M_L") (pin "5") (pinfunction "5_5") (pintype "passive"))
      (node (ref "U0") (pin "51") (pinfunction "PC10/UART4_TX/SDIO_D2_51") (pintype "bidirectional"))
    )
    (net (code "51") (name "/SPEED_R0") (class "Default")
      (node (ref "M_R") (pin "6") (pinfunction "6_6") (pintype "passive"))
      (node (ref "U0") (pin "62") (pinfunction "PB9/TIM4_CH4/SDIO_D5_62") (pintype "bidirectional"))
    )
    (net (code "52") (name "/SPEED_R1") (class "Default")
      (node (ref "M_R") (pin "5") (pinfunction "5_5") (pintype "passive"))
      (node (ref "U0") (pin "2") (pinfunction "PC13-TAMPER-RTC_2") (pintype "bidirectional"))
    )
    (net (code "53") (name "/STATE_1") (class "Default")
      (node (ref "U0") (pin "3") (pinfunction "PC14-OSC32_IN_3") (pintype "bidirectional"))
      (node (ref "U8") (pin "1") (pinfunction "1_1") (pintype "passive"))
    )
    (net (code "54") (name "/STATE_2") (class "Default")
      (node (ref "U0") (pin "4") (pinfunction "PC15-OSC32_OUT_4") (pintype "bidirectional"))
      (node (ref "U8") (pin "2") (pinfunction "2_2") (pintype "passive"))
    )
    (net (code "55") (name "/TX1") (class "Default")
      (node (ref "PH1") (pin "4") (pinfunction "4_4") (pintype "passive"))
      (node (ref "U0") (pin "42") (pinfunction "PA9/USART1_TX_42") (pintype "bidirectional"))
    )
    (net (code "56") (name "/USBDM") (class "Default")
      (node (ref "PH1") (pin "6") (pinfunction "6_6") (pintype "passive"))
      (node (ref "U0") (pin "44") (pinfunction "PA11/USART1_CTS/USBDM/CAN_RX_44") (pintype "bidirectional"))
    )
    (net (code "57") (name "/USBDP") (class "Default")
      (node (ref "PH1") (pin "5") (pinfunction "5_5") (pintype "passive"))
      (node (ref "U0") (pin "45") (pinfunction "PA12/USART1_RTS/USBDP/CAN_TX_45") (pintype "bidirectional"))
    )
    (net (code "58") (name "3.3V") (class "Default")
      (node (ref "C11") (pin "1") (pinfunction "1_1") (pintype "passive"))
      (node (ref "C12") (pin "2") (pinfunction "2_2") (pintype "passive"))
      (node (ref "C14") (pin "2") (pinfunction "2_2") (pintype "passive"))
      (node (ref "C15") (pin "2") (pinfunction "2_2") (pintype "passive"))
      (node (ref "C16") (pin "2") (pinfunction "2_2") (pintype "passive"))
      (node (ref "C17") (pin "2") (pinfunction "2_2") (pintype "passive"))
      (node (ref "C30") (pin "1") (pinfunction "1_1") (pintype "passive"))
      (node (ref "C35") (pin "1") (pinfunction "1_1") (pintype "passive"))
      (node (ref "C36") (pin "1") (pinfunction "1_1") (pintype "passive"))
      (node (ref "L0") (pin "1") (pinfunction "1_1") (pintype "passive"))
      (node (ref "R0") (pin "2") (pinfunction "2_2") (pintype "passive"))
      (node (ref "R19") (pin "2") (pinfunction "2_2") (pintype "passive"))
      (node (ref "R20") (pin "2") (pinfunction "2_2") (pintype "passive"))
      (node (ref "R21") (pin "2") (pinfunction "2_2") (pintype "passive"))
      (node (ref "R22") (pin "2") (pinfunction "2_2") (pintype "passive"))
      (node (ref "R31") (pin "1") (pinfunction "1_1") (pintype "passive"))
      (node (ref "R32") (pin "1") (pinfunction "1_1") (pintype "passive"))
      (node (ref "R33") (pin "1") (pinfunction "1_1") (pintype "passive"))
      (node (ref "R34") (pin "1") (pinfunction "1_1") (pintype "passive"))
      (node (ref "R35") (pin "1") (pinfunction "1_1") (pintype "passive"))
      (node (ref "R36") (pin "1") (pinfunction "1_1") (pintype "passive"))
      (node (ref "R53") (pin "2") (pinfunction "2_2") (pintype "passive"))
      (node (ref "R54") (pin "2") (pinfunction "2_2") (pintype "passive"))
      (node (ref "U0") (pin "1") (pinfunction "VBAT_1") (pintype "power_in"))
      (node (ref "U0") (pin "19") (pinfunction "VDD_4_19") (pintype "power_in"))
      (node (ref "U0") (pin "32") (pinfunction "VDD_1_32") (pintype "power_in"))
      (node (ref "U0") (pin "48") (pinfunction "VDD_2_48") (pintype "power_in"))
      (node (ref "U0") (pin "64") (pinfunction "VDD_3_64") (pintype "power_in"))
      (node (ref "U10") (pin "13") (pinfunction "VDD_13") (pintype "passive"))
      (node (ref "U10") (pin "8") (pinfunction "VLOGIC_8") (pintype "passive"))
      (node (ref "U2") (pin "5") (pinfunction "Vout_5") (pintype "passive"))
      (node (ref "U204") (pin "3") (pinfunction "~{WP}_3") (pintype "passive"))
      (node (ref "U204") (pin "7") (pinfunction "~{HOLD}_7") (pintype "passive"))
      (node (ref "U204") (pin "8") (pinfunction "VDD_8") (pintype "power_in"))
      (node (ref "U6") (pin "1") (pinfunction "1_1") (pintype "passive"))
      (node (ref "U6") (pin "2") (pinfunction "2_2") (pintype "passive"))
    )
    (net (code "59") (name "5V") (class "Default")
      (node (ref "C10") (pin "1") (pinfunction "1_1") (pintype "passive"))
      (node (ref "C24") (pin "2") (pinfunction "2_2") (pintype "passive"))
      (node (ref "LS1") (pin "1") (pinfunction "1_1") (pintype "passive"))
      (node (ref "M_L") (pin "4") (pinfunction "4_4") (pintype "passive"))
      (node (ref "M_R") (pin "4") (pinfunction "4_4") (pintype "passive"))
      (node (ref "PH1") (pin "8") (pinfunction "8_8") (pintype "passive"))
      (node (ref "R30") (pin "2") (pinfunction "2_2") (pintype "passive"))
      (node (ref "U1") (pin "5") (pinfunction "Vout_5") (pintype "passive"))
      (node (ref "U31") (pin "1") (pinfunction "A_1") (pintype "passive"))
      (node (ref "U32") (pin "1") (pinfunction "A_1") (pintype "passive"))
      (node (ref "U33") (pin "1") (pinfunction "A_1") (pintype "passive"))
      (node (ref "U34") (pin "1") (pinfunction "A_1") (pintype "passive"))
      (node (ref "U35") (pin "1") (pinfunction "A_1") (pintype "passive"))
      (node (ref "U36") (pin "1") (pinfunction "A_1") (pintype "passive"))
    )
    (net (code "60") (name "6.4V") (class "Default")
      (node (ref "C26") (pin "1") (pinfunction "1_1") (pintype "passive"))
      (node (ref "C29") (pin "1") (pinfunction "1_1") (pintype "passive"))
      (node (ref "C32") (pin "1") (pinfunction "1_1") (pintype "passive"))
      (node (ref "C38") (pin "1") (pinfunction "1_1") (pintype "passive"))
      (node (ref "L3") (pin "2") (pinfunction "2_2") (pintype "passive"))
      (node (ref "ML") (pin "2") (pinfunction "VCC_2") (pintype "passive"))
      (node (ref "ML") (pin "3") (pinfunction "VCC_3") (pintype "passive"))
      (node (ref "ML") (pin "6") (pinfunction "VREF_6") (pintype "passive"))
      (node (ref "MR") (pin "2") (pinfunction "VCC_2") (pintype "passive"))
      (node (ref "MR") (pin "3") (pinfunction "VCC_3") (pintype "passive"))
      (node (ref "MR") (pin "6") (pinfunction "VREF_6") (pintype "passive"))
      (node (ref "R51") (pin "2") (pinfunction "2_2") (pintype "passive"))
    )
    (net (code "61") (name "7.4V") (class "Default")
      (node (ref "C31") (pin "1") (pinfunction "1_1") (pintype "passive"))
      (node (ref "C8") (pin "1") (pinfunction "1_1") (pintype "passive"))
      (node (ref "C9") (pin "2") (pinfunction "2_2") (pintype "passive"))
      (node (ref "R24") (pin "2") (pinfunction "2_2") (pintype "passive"))
      (node (ref "S1") (pin "3") (pintype "passive"))
      (node (ref "U1") (pin "1") (pinfunction "Vin_1") (pintype "passive"))
      (node (ref "U1") (pin "3") (pinfunction "EN_3") (pintype "passive"))
      (node (ref "U2") (pin "1") (pinfunction "Vin_1") (pintype "passive"))
      (node (ref "U2") (pin "3") (pinfunction "EN_3") (pintype "passive"))
      (node (ref "U9") (pin "7") (pinfunction "VIN_7") (pintype "passive"))
    )
    (net (code "62") (name "GND") (class "Default")
      (node (ref "3.3V") (pin "2") (pinfunction "K_2") (pintype "passive"))
      (node (ref "C1") (pin "1") (pinfunction "1_1") (pintype "passive"))
      (node (ref "C10") (pin "2") (pinfunction "2_2") (pintype "passive"))
      (node (ref "C11") (pin "2") (pinfunction "2_2") (pintype "passive"))
      (node (ref "C12") (pin "1") (pinfunction "1_1") (pintype "passive"))
      (node (ref "C14") (pin "1") (pinfunction "1_1") (pintype "passive"))
      (node (ref "C15") (pin "1") (pinfunction "1_1") (pintype "passive"))
      (node (ref "C16") (pin "1") (pinfunction "1_1") (pintype "passive"))
      (node (ref "C17") (pin "1") (pinfunction "1_1") (pintype "passive"))
      (node (ref "C24") (pin "1") (pinfunction "1_1") (pintype "passive"))
      (node (ref "C26") (pin "2") (pinfunction "2_2") (pintype "passive"))
      (node (ref "C29") (pin "2") (pinfunction "2_2") (pintype "passive"))
      (node (ref "C30") (pin "2") (pinfunction "2_2") (pintype "passive"))
      (node (ref "C31") (pin "2") (pinfunction "2_2") (pintype "passive"))
      (node (ref "C32") (pin "2") (pinfunction "2_2") (pintype "passive"))
      (node (ref "C33") (pin "2") (pinfunction "2_2") (pintype "passive"))
      (node (ref "C34") (pin "1") (pinfunction "1_1") (pintype "passive"))
      (node (ref "C35") (pin "2") (pinfunction "2_2") (pintype "passive"))
      (node (ref "C36") (pin "2") (pinfunction "2_2") (pintype "passive"))
      (node (ref "C38") (pin "2") (pinfunction "2_2") (pintype "passive"))
      (node (ref "C5") (pin "1") (pinfunction "1_1") (pintype "passive"))
      (node (ref "C8") (pin "2") (pinfunction "2_2") (pintype "passive"))
      (node (ref "C9") (pin "1") (pinfunction "1_1") (pintype "passive"))
      (node (ref "D10") (pin "1") (pinfunction "A_1") (pintype "passive"))
      (node (ref "JP22") (pin "1") (pinfunction "1_1") (pintype "passive"))
      (node (ref "JP22") (pin "10") (pinfunction "10_10") (pintype "passive"))
      (node (ref "JP22") (pin "11") (pinfunction "11_11") (pintype "passive"))
      (node (ref "JP22") (pin "12") (pinfunction "12_12") (pintype "passive"))
      (node (ref "JP22") (pin "13") (pinfunction "13_13") (pintype "passive"))
      (node (ref "JP22") (pin "14") (pinfunction "14_14") (pintype "passive"))
      (node (ref "JP22") (pin "2") (pinfunction "2_2") (pintype "passive"))
      (node (ref "JP22") (pin "3") (pinfunction "3_3") (pintype "passive"))
      (node (ref "JP22") (pin "4") (pinfunction "4_4") (pintype "passive"))
      (node (ref "JP22") (pin "5") (pinfunction "5_5") (pintype "passive"))
      (node (ref "JP22") (pin "6") (pinfunction "6_6") (pintype "passive"))
      (node (ref "JP22") (pin "7") (pinfunction "7_7") (pintype "passive"))
      (node (ref "JP22") (pin "8") (pinfunction "8_8") (pintype "passive"))
      (node (ref "JP22") (pin "9") (pinfunction "9_9") (pintype "passive"))
      (node (ref "M_L") (pin "3") (pinfunction "3_3") (pintype "passive"))
      (node (ref "M_R") (pin "3") (pinfunction "3_3") (pintype "passive"))
      (node (ref "PH1") (pin "7") (pinfunction "7_7") (pintype "passive"))
      (node (ref "PH2") (pin "1") (pinfunction "1_1") (pintype "passive"))
      (node (ref "PH2") (pin "2") (pinfunction "2_2") (pintype "passive"))
      (node (ref "PH2") (pin "3") (pinfunction "3_3") (pintype "passive"))
      (node (ref "PH2") (pin "4") (pinfunction "4_4") (pintype "passive"))
      (node (ref "R10") (pin "2") (pinfunction "2_2") (pintype "passive"))
      (node (ref "R17") (pin "2") (pinfunction "2_2") (pintype "passive"))
      (node (ref "R18") (pin "2") (pinfunction "2_2") (pintype "passive"))
      (node (ref "R23") (pin "1") (pinfunction "1_1") (pintype "passive"))
      (node (ref "R25") (pin "1") (pinfunction "1_1") (pintype "passive"))
      (node (ref "R26") (pin "2") (pinfunction "2_2") (pintype "passive"))
      (node (ref "R27") (pin "2") (pinfunction "2_2") (pintype "passive"))
      (node (ref "R52") (pin "1") (pinfunction "1_1") (pintype "passive"))
      (node (ref "R55") (pin "1") (pinfunction "1_1") (pintype "passive"))
      (node (ref "R9") (pin "2") (pinfunction "2_2") (pintype "passive"))
      (node (ref "RESET") (pin "2") (pinfunction "2_2") (pintype "passive"))
      (node (ref "U0") (pin "12") (pinfunction "VSSA_12") (pintype "power_in"))
      (node (ref "U0") (pin "18") (pinfunction "VSS_4_18") (pintype "power_in"))
      (node (ref "U0") (pin "31") (pinfunction "VSS_1_31") (pintype "power_in"))
      (node (ref "U0") (pin "47") (pinfunction "VSS_2_47") (pintype "power_in"))
      (node (ref "U0") (pin "63") (pinfunction "VSS_3_63") (pintype "power_in"))
      (node (ref "U1") (pin "2") (pinfunction "GND_2") (pintype "passive"))
      (node (ref "U10") (pin "1") (pinfunction "CLKIN_1") (pintype "passive"))
      (node (ref "U10") (pin "11") (pinfunction "FSYNC_11") (pintype "passive"))
      (node (ref "U10") (pin "18") (pinfunction "GND_18") (pintype "passive"))
      (node (ref "U2") (pin "2") (pinfunction "GND_2") (pintype "passive"))
      (node (ref "U204") (pin "4") (pinfunction "VSS_4") (pintype "power_in"))
      (node (ref "U30") (pin "8") (pinfunction "GND_8") (pintype "power_in"))
      (node (ref "U31") (pin "3") (pinfunction "E_3") (pintype "passive"))
      (node (ref "U32") (pin "3") (pinfunction "E_3") (pintype "passive"))
      (node (ref "U33") (pin "3") (pinfunction "E_3") (pintype "passive"))
      (node (ref "U34") (pin "3") (pinfunction "E_3") (pintype "passive"))
      (node (ref "U35") (pin "3") (pinfunction "E_3") (pintype "passive"))
      (node (ref "U36") (pin "3") (pinfunction "E_3") (pintype "passive"))
      (node (ref "U5") (pin "7") (pinfunction "GND_7") (pintype "power_in"))
      (node (ref "U6") (pin "10") (pinfunction "10_10") (pintype "passive"))
      (node (ref "U8") (pin "3") (pinfunction "3_3") (pintype "passive"))
      (node (ref "U8") (pin "4") (pinfunction "4_4") (pintype "passive"))
      (node (ref "U9") (pin "6") (pinfunction "GND_6") (pintype "passive"))
    )
    (net (code "63") (name "Net-(3.3V-A)") (class "Default")
      (node (ref "3.3V") (pin "1") (pinfunction "A_1") (pintype "passive"))
      (node (ref "R30") (pin "1") (pinfunction "1_1") (pintype "passive"))
    )
    (net (code "64") (name "Net-(D10-K)") (class "Default")
      (node (ref "C25") (pin "1") (pinfunction "1_1") (pintype "passive"))
      (node (ref "D10") (pin "2") (pinfunction "K_2") (pintype "passive"))
      (node (ref "L3") (pin "1") (pinfunction "1_1") (pintype "passive"))
      (node (ref "U9") (pin "8") (pinfunction "PH_8") (pintype "passive"))
    )
    (net (code "65") (name "Net-(JP23-Pad1)") (class "Default")
      (node (ref "JP23") (pin "1") (pinfunction "1_1") (pintype "passive"))
      (node (ref "JP23") (pin "10") (pinfunction "10_10") (pintype "passive"))
      (node (ref "JP23") (pin "11") (pinfunction "11_11") (pintype "passive"))
      (node (ref "JP23") (pin "12") (pinfunction "12_12") (pintype "passive"))
      (node (ref "JP23") (pin "13") (pinfunction "13_13") (pintype "passive"))
      (node (ref "JP23") (pin "14") (pinfunction "14_14") (pintype "passive"))
      (node (ref "JP23") (pin "2") (pinfunction "2_2") (pintype "passive"))
      (node (ref "JP23") (pin "3") (pinfunction "3_3") (pintype "passive"))
      (node (ref "JP23") (pin "4") (pinfunction "4_4") (pintype "passive"))
      (node (ref "JP23") (pin "5") (pinfunction "5_5") (pintype "passive"))
      (node (ref "JP23") (pin "6") (pinfunction "6_6") (pintype "passive"))
      (node (ref "JP23") (pin "7") (pinfunction "7_7") (pintype "passive"))
      (node (ref "JP23") (pin "8") (pinfunction "8_8") (pintype "passive"))
      (node (ref "JP23") (pin "9") (pinfunction "9_9") (pintype "passive"))
    )
    (net (code "66") (name "Net-(JP24-Pad1)") (class "Default")
      (node (ref "JP24") (pin "1") (pinfunction "1_1") (pintype "passive"))
      (node (ref "JP24") (pin "10") (pinfunction "10_10") (pintype "passive"))
      (node (ref "JP24") (pin "11") (pinfunction "11_11") (pintype "passive"))
      (node (ref "JP24") (pin "12") (pinfunction "12_12") (pintype "passive"))
      (node (ref "JP24") (pin "13") (pinfunction "13_13") (pintype "passive"))
      (node (ref "JP24") (pin "14") (pinfunction "14_14") (pintype "passive"))
      (node (ref "JP24") (pin "2") (pinfunction "2_2") (pintype "passive"))
      (node (ref "JP24") (pin "3") (pinfunction "3_3") (pintype "passive"))
      (node (ref "JP24") (pin "4") (pinfunction "4_4") (pintype "passive"))
      (node (ref "JP24") (pin "5") (pinfunction "5_5") (pintype "passive"))
      (node (ref "JP24") (pin "6") (pinfunction "6_6") (pintype "passive"))
      (node (ref "JP24") (pin "7") (pinfunction "7_7") (pintype "passive"))
      (node (ref "JP24") (pin "8") (pinfunction "8_8") (pintype "passive"))
      (node (ref "JP24") (pin "9") (pinfunction "9_9") (pintype "passive"))
    )
    (net (code "67") (name "Net-(LED1-K)") (class "Default")
      (node (ref "LED1") (pin "2") (pinfunction "K_2") (pintype "passive"))
      (node (ref "R18") (pin "1") (pinfunction "1_1") (pintype "passive"))
    )
    (net (code "68") (name "Net-(LED2-K)") (class "Default")
      (node (ref "LED2") (pin "2") (pinfunction "K_2") (pintype "passive"))
      (node (ref "R17") (pin "1") (pinfunction "1_1") (pintype "passive"))
    )
    (net (code "69") (name "Net-(LS1-Pad2)") (class "Default")
      (node (ref "LS1") (pin "2") (pinfunction "2_2") (pintype "passive"))
      (node (ref "R40") (pin "2") (pinfunction "2_2") (pintype "passive"))
    )
    (net (code "70") (name "Net-(ML-FIN)") (class "Default")
      (node (ref "ML") (pin "4") (pinfunction "FIN_4") (pintype "passive"))
      (node (ref "U5") (pin "3") (pinfunction "Y_3") (pintype "output"))
    )
    (net (code "71") (name "Net-(ML-RIN)") (class "Default")
      (node (ref "ML") (pin "5") (pinfunction "RIN_5") (pintype "passive"))
      (node (ref "U5") (pin "6") (pinfunction "Y_6") (pintype "output"))
    )
    (net (code "72") (name "Net-(MR-FIN)") (class "Default")
      (node (ref "MR") (pin "4") (pinfunction "FIN_4") (pintype "passive"))
      (node (ref "U5") (pin "8") (pinfunction "Y_8") (pintype "output"))
    )
    (net (code "73") (name "Net-(MR-RIN)") (class "Default")
      (node (ref "MR") (pin "5") (pinfunction "RIN_5") (pintype "passive"))
      (node (ref "U5") (pin "11") (pinfunction "Y_11") (pintype "output"))
    )
    (net (code "74") (name "Net-(U0-OSC_IN{slash}PD0)") (class "Default")
      (node (ref "R1") (pin "2") (pinfunction "2_2") (pintype "passive"))
      (node (ref "U0") (pin "5") (pinfunction "OSC_IN/PD0_5") (pintype "input"))
      (node (ref "Y1") (pin "1") (pinfunction "OSC1_1") (pintype "passive"))
    )
    (net (code "75") (name "Net-(U0-OSC_OUT{slash}PD1)") (class "Default")
      (node (ref "R1") (pin "1") (pinfunction "1_1") (pintype "passive"))
      (node (ref "U0") (pin "6") (pinfunction "OSC_OUT/PD1_6") (pintype "output"))
      (node (ref "Y1") (pin "2") (pinfunction "OSC2_2") (pintype "passive"))
    )
    (net (code "76") (name "Net-(U0-VDDA)") (class "Default")
      (node (ref "C5") (pin "2") (pinfunction "2_2") (pintype "passive"))
      (node (ref "L0") (pin "2") (pinfunction "2_2") (pintype "passive"))
      (node (ref "U0") (pin "13") (pinfunction "VDDA_13") (pintype "power_in"))
    )
    (net (code "77") (name "Net-(U9-BOOT)") (class "Default")
      (node (ref "C25") (pin "2") (pinfunction "2_2") (pintype "passive"))
      (node (ref "U9") (pin "1") (pinfunction "BOOT_1") (pintype "passive"))
    )
    (net (code "78") (name "Net-(U9-VSENSE)") (class "Default")
      (node (ref "R51") (pin "1") (pinfunction "1_1") (pintype "passive"))
      (node (ref "R52") (pin "2") (pinfunction "2_2") (pintype "passive"))
      (node (ref "U9") (pin "4") (pinfunction "VSENSE_4") (pintype "passive"))
    )
    (net (code "79") (name "Net-(U10-AD0)") (class "Default")
      (node (ref "R55") (pin "2") (pinfunction "2_2") (pintype "passive"))
      (node (ref "U10") (pin "9") (pinfunction "AD0_9") (pintype "passive"))
    )
    (net (code "80") (name "Net-(U10-CPOUT)") (class "Default")
      (node (ref "C34") (pin "2") (pinfunction "2_2") (pintype "passive"))
      (node (ref "U10") (pin "20") (pinfunction "CPOUT_20") (pintype "passive"))
    )
    (net (code "81") (name "Net-(U10-REGOUT)") (class "Default")
      (node (ref "C33") (pin "1") (pinfunction "1_1") (pintype "passive"))
      (node (ref "U10") (pin "10") (pinfunction "REGOUT_10") (pintype "passive"))
    )
    (net (code "82") (name "Net-(U30-OUT1)") (class "Default")
      (node (ref "R46") (pin "1") (pinfunction "1_1") (pintype "passive"))
      (node (ref "U30") (pin "16") (pinfunction "OUT1_16") (pintype "open_collector"))
    )
    (net (code "83") (name "Net-(U30-OUT2)") (class "Default")
      (node (ref "R45") (pin "1") (pinfunction "1_1") (pintype "passive"))
      (node (ref "U30") (pin "15") (pinfunction "OUT2_15") (pintype "open_collector"))
    )
    (net (code "84") (name "Net-(U30-OUT3)") (class "Default")
      (node (ref "R44") (pin "1") (pinfunction "1_1") (pintype "passive"))
      (node (ref "U30") (pin "14") (pinfunction "OUT3_14") (pintype "open_collector"))
    )
    (net (code "85") (name "Net-(U30-OUT4)") (class "Default")
      (node (ref "R43") (pin "1") (pinfunction "1_1") (pintype "passive"))
      (node (ref "U30") (pin "13") (pinfunction "OUT4_13") (pintype "open_collector"))
    )
    (net (code "86") (name "Net-(U30-OUT5)") (class "Default")
      (node (ref "R42") (pin "1") (pinfunction "1_1") (pintype "passive"))
      (node (ref "U30") (pin "12") (pinfunction "OUT5_12") (pintype "open_collector"))
    )
    (net (code "87") (name "Net-(U30-OUT7)") (class "Default")
      (node (ref "R41") (pin "1") (pinfunction "1_1") (pintype "passive"))
      (node (ref "U30") (pin "10") (pinfunction "OUT7_10") (pintype "open_collector"))
    )
    (net (code "88") (name "Net-(U31-K)") (class "Default")
      (node (ref "R43") (pin "2") (pinfunction "2_2") (pintype "passive"))
      (node (ref "U31") (pin "2") (pinfunction "K_2") (pintype "passive"))
    )
    (net (code "89") (name "Net-(U32-K)") (class "Default")
      (node (ref "R42") (pin "2") (pinfunction "2_2") (pintype "passive"))
      (node (ref "U32") (pin "2") (pinfunction "K_2") (pintype "passive"))
    )
    (net (code "90") (name "Net-(U33-K)") (class "Default")
      (node (ref "R41") (pin "2") (pinfunction "2_2") (pintype "passive"))
      (node (ref "U33") (pin "2") (pinfunction "K_2") (pintype "passive"))
    )
    (net (code "91") (name "Net-(U34-K)") (class "Default")
      (node (ref "R46") (pin "2") (pinfunction "2_2") (pintype "passive"))
      (node (ref "U34") (pin "2") (pinfunction "K_2") (pintype "passive"))
    )
    (net (code "92") (name "Net-(U35-K)") (class "Default")
      (node (ref "R45") (pin "2") (pinfunction "2_2") (pintype "passive"))
      (node (ref "U35") (pin "2") (pinfunction "K_2") (pintype "passive"))
    )
    (net (code "93") (name "Net-(U36-K)") (class "Default")
      (node (ref "R44") (pin "2") (pinfunction "2_2") (pintype "passive"))
      (node (ref "U36") (pin "2") (pinfunction "K_2") (pintype "passive"))
    )
    (net (code "94") (name "VDD") (class "Default")
      (node (ref "U5") (pin "14") (pinfunction "VDD_14") (pintype "power_in"))
    )
    (net (code "95") (name "unconnected-(JP21-Pad15)") (class "Default")
      (node (ref "JP21") (pin "15") (pinfunction "15_15") (pintype "passive"))
    )
    (net (code "96") (name "unconnected-(JP21-Pad16)") (class "Default")
      (node (ref "JP21") (pin "16") (pinfunction "16_16") (pintype "passive"))
    )
    (net (code "97") (name "unconnected-(JP21-Pad17)") (class "Default")
      (node (ref "JP21") (pin "17") (pinfunction "17_17") (pintype "passive"))
    )
    (net (code "98") (name "unconnected-(JP21-Pad18)") (class "Default")
      (node (ref "JP21") (pin "18") (pinfunction "18_18") (pintype "passive"))
    )
    (net (code "99") (name "unconnected-(JP21-Pad19)") (class "Default")
      (node (ref "JP21") (pin "19") (pinfunction "19_19") (pintype "passive"))
    )
    (net (code "100") (name "unconnected-(JP21-Pad20)") (class "Default")
      (node (ref "JP21") (pin "20") (pinfunction "20_20") (pintype "passive"))
    )
    (net (code "101") (name "unconnected-(JP22-Pad15)") (class "Default")
      (node (ref "JP22") (pin "15") (pinfunction "15_15") (pintype "passive"))
    )
    (net (code "102") (name "unconnected-(JP22-Pad16)") (class "Default")
      (node (ref "JP22") (pin "16") (pinfunction "16_16") (pintype "passive"))
    )
    (net (code "103") (name "unconnected-(JP22-Pad17)") (class "Default")
      (node (ref "JP22") (pin "17") (pinfunction "17_17") (pintype "passive"))
    )
    (net (code "104") (name "unconnected-(JP22-Pad18)") (class "Default")
      (node (ref "JP22") (pin "18") (pinfunction "18_18") (pintype "passive"))
    )
    (net (code "105") (name "unconnected-(JP22-Pad19)") (class "Default")
      (node (ref "JP22") (pin "19") (pinfunction "19_19") (pintype "passive"))
    )
    (net (code "106") (name "unconnected-(JP22-Pad20)") (class "Default")
      (node (ref "JP22") (pin "20") (pinfunction "20_20") (pintype "passive"))
    )
    (net (code "107") (name "unconnected-(JP23-Pad15)") (class "Default")
      (node (ref "JP23") (pin "15") (pinfunction "15_15") (pintype "passive"))
    )
    (net (code "108") (name "unconnected-(JP23-Pad16)") (class "Default")
      (node (ref "JP23") (pin "16") (pinfunction "16_16") (pintype "passive"))
    )
    (net (code "109") (name "unconnected-(JP23-Pad17)") (class "Default")
      (node (ref "JP23") (pin "17") (pinfunction "17_17") (pintype "passive"))
    )
    (net (code "110") (name "unconnected-(JP23-Pad18)") (class "Default")
      (node (ref "JP23") (pin "18") (pinfunction "18_18") (pintype "passive"))
    )
    (net (code "111") (name "unconnected-(JP23-Pad19)") (class "Default")
      (node (ref "JP23") (pin "19") (pinfunction "19_19") (pintype "passive"))
    )
    (net (code "112") (name "unconnected-(JP23-Pad20)") (class "Default")
      (node (ref "JP23") (pin "20") (pinfunction "20_20") (pintype "passive"))
    )
    (net (code "113") (name "unconnected-(JP24-Pad15)") (class "Default")
      (node (ref "JP24") (pin "15") (pinfunction "15_15") (pintype "passive"))
    )
    (net (code "114") (name "unconnected-(JP24-Pad16)") (class "Default")
      (node (ref "JP24") (pin "16") (pinfunction "16_16") (pintype "passive"))
    )
    (net (code "115") (name "unconnected-(JP24-Pad17)") (class "Default")
      (node (ref "JP24") (pin "17") (pinfunction "17_17") (pintype "passive"))
    )
    (net (code "116") (name "unconnected-(JP24-Pad18)") (class "Default")
      (node (ref "JP24") (pin "18") (pinfunction "18_18") (pintype "passive"))
    )
    (net (code "117") (name "unconnected-(JP24-Pad19)") (class "Default")
      (node (ref "JP24") (pin "19") (pinfunction "19_19") (pintype "passive"))
    )
    (net (code "118") (name "unconnected-(JP24-Pad20)") (class "Default")
      (node (ref "JP24") (pin "20") (pinfunction "20_20") (pintype "passive"))
    )
    (net (code "119") (name "unconnected-(S1-Pad1)") (class "Default")
      (node (ref "S1") (pin "1") (pintype "passive"))
    )
    (net (code "120") (name "unconnected-(U1-ADJ{slash}BYP-Pad4)") (class "Default")
      (node (ref "U1") (pin "4") (pinfunction "ADJ/BYP_4") (pintype "passive"))
    )
    (net (code "121") (name "unconnected-(U2-ADJ{slash}BYP-Pad4)") (class "Default")
      (node (ref "U2") (pin "4") (pinfunction "ADJ/BYP_4") (pintype "passive"))
    )
    (net (code "122") (name "unconnected-(U6-Pad8)") (class "Default")
      (node (ref "U6") (pin "8") (pinfunction "8_8") (pintype "passive"))
    )
    (net (code "123") (name "unconnected-(U9-ENA-Pad5)") (class "Default")
      (node (ref "U9") (pin "5") (pinfunction "ENA_5") (pintype "passive"))
    )
    (net (code "124") (name "unconnected-(U9-NC-Pad2)") (class "Default")
      (node (ref "U9") (pin "2") (pinfunction "NC_2") (pintype "passive"))
    )
    (net (code "125") (name "unconnected-(U9-NC-Pad3)") (class "Default")
      (node (ref "U9") (pin "3") (pinfunction "NC_3") (pintype "passive"))
    )
    (net (code "126") (name "unconnected-(U10-AUX_CL-Pad7)") (class "Default")
      (node (ref "U10") (pin "7") (pinfunction "AUX_CL_7") (pintype "passive"))
    )
    (net (code "127") (name "unconnected-(U10-AUX_DA-Pad6)") (class "Default")
      (node (ref "U10") (pin "6") (pinfunction "AUX_DA_6") (pintype "passive"))
    )
    (net (code "128") (name "unconnected-(U10-NC-Pad2)") (class "Default")
      (node (ref "U10") (pin "2") (pinfunction "NC_2") (pintype "passive"))
    )
    (net (code "129") (name "unconnected-(U10-NC-Pad3)") (class "Default")
      (node (ref "U10") (pin "3") (pinfunction "NC_3") (pintype "passive"))
    )
    (net (code "130") (name "unconnected-(U10-NC-Pad4)") (class "Default")
      (node (ref "U10") (pin "4") (pinfunction "NC_4") (pintype "passive"))
    )
    (net (code "131") (name "unconnected-(U10-NC-Pad5)") (class "Default")
      (node (ref "U10") (pin "5") (pinfunction "NC_5") (pintype "passive"))
    )
    (net (code "132") (name "unconnected-(U10-NC-Pad14)") (class "Default")
      (node (ref "U10") (pin "14") (pinfunction "NC_14") (pintype "passive"))
    )
    (net (code "133") (name "unconnected-(U10-NC-Pad15)") (class "Default")
      (node (ref "U10") (pin "15") (pinfunction "NC_15") (pintype "passive"))
    )
    (net (code "134") (name "unconnected-(U10-NC-Pad16)") (class "Default")
      (node (ref "U10") (pin "16") (pinfunction "NC_16") (pintype "passive"))
    )
    (net (code "135") (name "unconnected-(U10-NC-Pad17)") (class "Default")
      (node (ref "U10") (pin "17") (pinfunction "NC_17") (pintype "passive"))
    )
    (net (code "136") (name "unconnected-(U10-RESV-Pad19)") (class "Default")
      (node (ref "U10") (pin "19") (pinfunction "RESV_19") (pintype "passive"))
    )
    (net (code "137") (name "unconnected-(U10-RESV-Pad21)") (class "Default")
      (node (ref "U10") (pin "21") (pinfunction "RESV_21") (pintype "passive"))
    )
    (net (code "138") (name "unconnected-(U10-RESV-Pad22)") (class "Default")
      (node (ref "U10") (pin "22") (pinfunction "RESV_22") (pintype "passive"))
    )
    (net (code "139") (name "unconnected-(U30-COM-Pad9)") (class "Default")
      (node (ref "U30") (pin "9") (pinfunction "COM_9") (pintype "passive"))
    )
  )
)
